# encoder.net
KiCad netlist of a schematic drawn in EAGLE
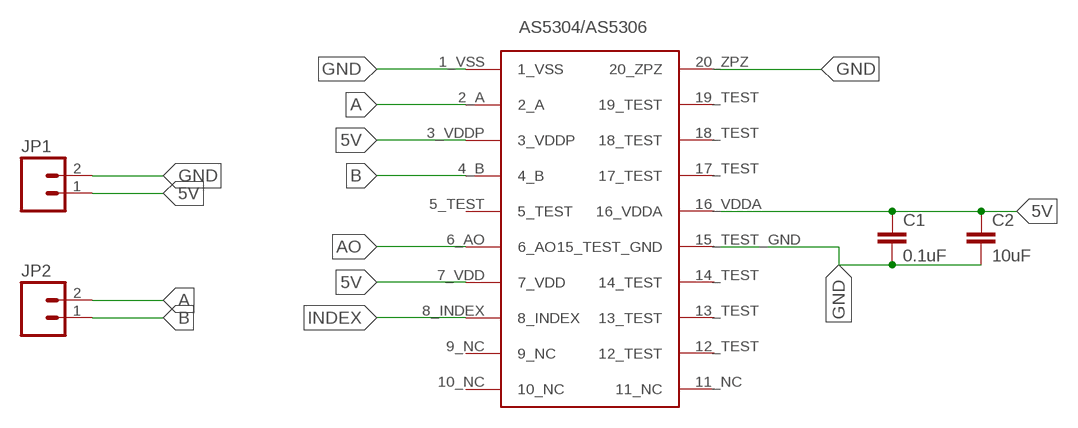
[diagram p0: schematic, sheet 1]

(export (version "E")
  (design (tool "Eeschema 10.0.6"))
  (components
    (comp (ref "C1")
      (value "0.1uF")
      (footprint "eagle-import:C0603")
      (libsource (lib "eagle-import") (part "C-EUC0603"))
    )
    (comp (ref "C2")
      (value "10uF")
      (footprint "eagle-import:C0603")
      (libsource (lib "eagle-import") (part "C-EUC0603"))
    )
    (comp (ref "JP1")
      (value "M02LOCK")
      (footprint "eagle-import:1X02_LOCK")
      (libsource (lib "eagle-import") (part "M02LOCK"))
    )
    (comp (ref "JP2")
      (value "M02LOCK")
      (footprint "eagle-import:1X02_LOCK")
      (libsource (lib "eagle-import") (part "M02LOCK"))
    )
    (comp (ref "U$1")
      (value "AS5304/AS5306-ENCODER")
      (footprint "eagle-import:AS5304_AS5306-ENCODER")
      (libsource (lib "eagle-import") (part "AS5304/AS5306-ENCODER"))
    )
  )
  (nets
    (net (code "1") (name "5V") (class "Default")
      (node (ref "C1") (pin "1") (pinfunction "1_1") (pintype "passive"))
      (node (ref "C2") (pin "1") (pinfunction "1_1") (pintype "passive"))
      (node (ref "JP1") (pin "1") (pinfunction "1_1") (pintype "passive"))
      (node (ref "U$1") (pin "16_VDDA") (pinfunction "16_VDDA_16_VDDA") (pintype "bidirectional"))
      (node (ref "U$1") (pin "3_VDDP") (pinfunction "3_VDDP_3_VDDP") (pintype "bidirectional"))
      (node (ref "U$1") (pin "7_VDD") (pinfunction "7_VDD_7_VDD") (pintype "bidirectional"))
    )
    (net (code "2") (name "A") (class "Default")
      (node (ref "JP2") (pin "2") (pinfunction "2_2") (pintype "passive"))
      (node (ref "U$1") (pin "2_A") (pinfunction "2_A_2_A") (pintype "bidirectional"))
    )
    (net (code "3") (name "AO") (class "Default")
      (node (ref "U$1") (pin "6_AO") (pinfunction "6_AO_6_AO") (pintype "bidirectional"))
    )
    (net (code "4") (name "B") (class "Default")
      (node (ref "JP2") (pin "1") (pinfunction "1_1") (pintype "passive"))
      (node (ref "U$1") (pin "4_B") (pinfunction "4_B_4_B") (pintype "bidirectional"))
    )
    (net (code "5") (name "GND") (class "Default")
      (node (ref "C1") (pin "2") (pinfunction "2_2") (pintype "passive"))
      (node (ref "C2") (pin "2") (pinfunction "2_2") (pintype "passive"))
      (node (ref "JP1") (pin "2") (pinfunction "2_2") (pintype "passive"))
      (node (ref "U$1") (pin "15_TEST_GND") (pinfunction "15_TEST_GND_15_TEST_GND") (pintype "bidirectional"))
      (node (ref "U$1") (pin "1_VSS") (pinfunction "1_VSS_1_VSS") (pintype "bidirectional"))
      (node (ref "U$1") (pin "20_ZPZ") (pinfunction "20_ZPZ_20_ZPZ") (pintype "bidirectional"))
    )
    (net (code "6") (name "INDEX") (class "Default")
      (node (ref "U$1") (pin "8_INDEX") (pinfunction "8_INDEX_8_INDEX") (pintype "bidirectional"))
    )
    (net (code "7") (name "unconnected-(U$1-Pad5_TEST)") (class "Default")
      (node (ref "U$1") (pin "5_TEST") (pinfunction "5_TEST_5_TEST") (pintype "no_connect"))
    )
    (net (code "8") (name "unconnected-(U$1-Pad9_NC)") (class "Default")
      (node (ref "U$1") (pin "9_NC") (pinfunction "9_NC_9_NC") (pintype "no_connect"))
    )
    (net (code "9") (name "unconnected-(U$1-Pad10_NC)") (class "Default")
      (node (ref "U$1") (pin "10_NC") (pinfunction "10_NC_10_NC") (pintype "no_connect"))
    )
    (net (code "10") (name "unconnected-(U$1-Pad11_NC)") (class "Default")
      (node (ref "U$1") (pin "11_NC") (pinfunction "11_NC_11_NC") (pintype "no_connect"))
    )
    (net (code "11") (name "unconnected-(U$1-Pad12_TEST)") (class "Default")
      (node (ref "U$1") (pin "12_TEST") (pinfunction "12_TEST_12_TEST") (pintype "no_connect"))
    )
    (net (code "12") (name "unconnected-(U$1-Pad13_TEST)") (class "Default")
      (node (ref "U$1") (pin "13_TEST") (pinfunction "13_TEST_13_TEST") (pintype "no_connect"))
    )
    (net (code "13") (name "unconnected-(U$1-Pad14_TEST)") (class "Default")
      (node (ref "U$1") (pin "14_TEST") (pinfunction "14_TEST_14_TEST") (pintype "bidirectional"))
    )
    (net (code "14") (name "unconnected-(U$1-Pad17_TEST)") (class "Default")
      (node (ref "U$1") (pin "17_TEST") (pinfunction "17_TEST_17_TEST") (pintype "no_connect"))
    )
    (net (code "15") (name "unconnected-(U$1-Pad18_TEST)") (class "Default")
      (node (ref "U$1") (pin "18_TEST") (pinfunction "18_TEST_18_TEST") (pintype "no_connect"))
    )
    (net (code "16") (name "unconnected-(U$1-Pad19_TEST)") (class "Default")
      (node (ref "U$1") (pin "19_TEST") (pinfunction "19_TEST_19_TEST") (pintype "no_connect"))
    )
  )
)
